# Arduino101BiomedDevBoard.net
KiCad netlist of a schematic drawn in EAGLE
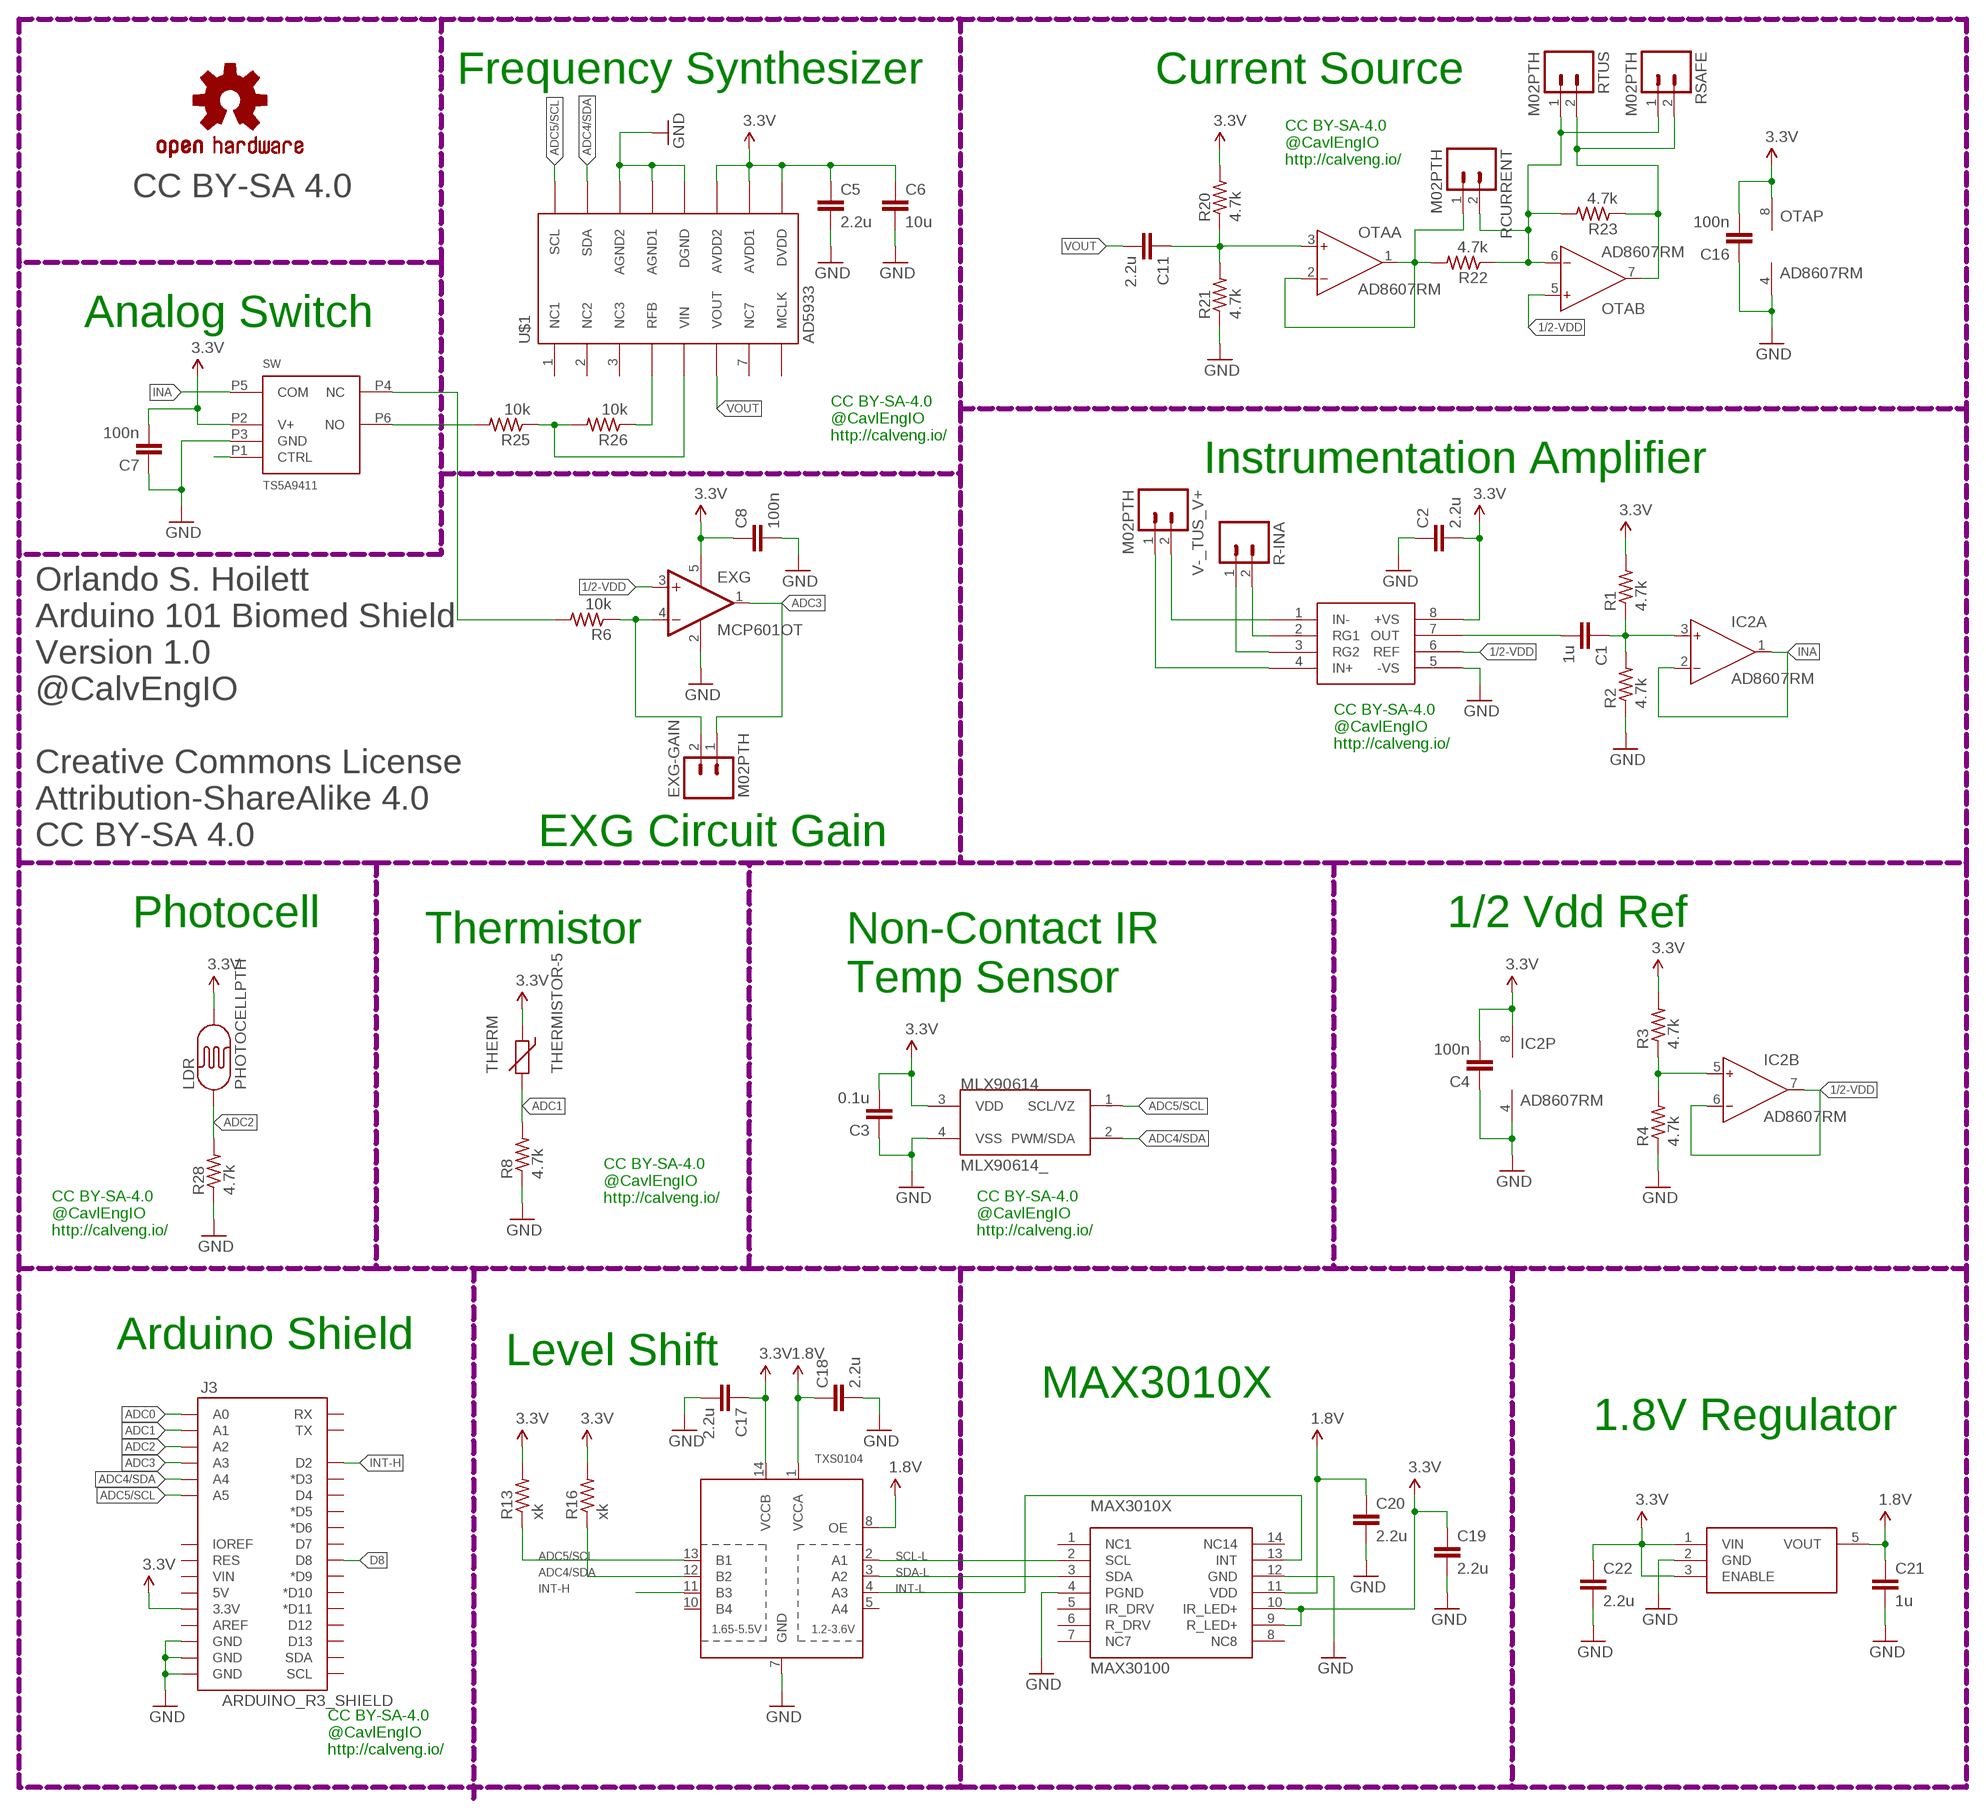
[diagram p0: schematic, sheet 1]

(export (version "E")
  (design (tool "Eeschema 10.0.6"))
  (components
    (comp (ref "1.8V")
      (value "MIC5504")
      (footprint "eagle-import:SOT23-5")
      (libsource (lib "eagle-import") (part "MIC5504"))
    )
    (comp (ref "C1")
      (value "1u")
      (footprint "eagle-import:C0402")
      (libsource (lib "eagle-import") (part "C-EUC0402"))
    )
    (comp (ref "C2")
      (value "2.2u")
      (footprint "eagle-import:C0402")
      (libsource (lib "eagle-import") (part "C-EUC0402"))
    )
    (comp (ref "C3")
      (value "0.1u")
      (footprint "eagle-import:C0402")
      (libsource (lib "eagle-import") (part "C-EUC0402"))
    )
    (comp (ref "C4")
      (value "100n")
      (footprint "eagle-import:C0402")
      (libsource (lib "eagle-import") (part "C-EUC0402"))
    )
    (comp (ref "C5")
      (value "2.2u")
      (footprint "eagle-import:C0402")
      (libsource (lib "eagle-import") (part "C-EUC0402"))
    )
    (comp (ref "C6")
      (value "10u")
      (footprint "eagle-import:C0805")
      (libsource (lib "eagle-import") (part "C-EUC0805"))
    )
    (comp (ref "C7")
      (value "100n")
      (footprint "eagle-import:C0402")
      (libsource (lib "eagle-import") (part "C-EUC0402"))
    )
    (comp (ref "C8")
      (value "100n")
      (footprint "eagle-import:C0402")
      (libsource (lib "eagle-import") (part "C-EUC0402"))
    )
    (comp (ref "C11")
      (value "2.2u")
      (footprint "eagle-import:C0402")
      (libsource (lib "eagle-import") (part "C-EUC0402"))
    )
    (comp (ref "C16")
      (value "100n")
      (footprint "eagle-import:C0402")
      (libsource (lib "eagle-import") (part "C-EUC0402"))
    )
    (comp (ref "C17")
      (value "2.2u")
      (footprint "eagle-import:C0402")
      (libsource (lib "eagle-import") (part "C-EUC0402"))
    )
    (comp (ref "C18")
      (value "2.2u")
      (footprint "eagle-import:C0402")
      (libsource (lib "eagle-import") (part "C-EUC0402"))
    )
    (comp (ref "C19")
      (value "2.2u")
      (footprint "eagle-import:C0402")
      (libsource (lib "eagle-import") (part "C-EUC0402"))
    )
    (comp (ref "C20")
      (value "2.2u")
      (footprint "eagle-import:C0402")
      (libsource (lib "eagle-import") (part "C-EUC0402"))
    )
    (comp (ref "C21")
      (value "1u")
      (footprint "eagle-import:C0402")
      (libsource (lib "eagle-import") (part "C-EUC0402"))
    )
    (comp (ref "C22")
      (value "2.2u")
      (footprint "eagle-import:C0402")
      (libsource (lib "eagle-import") (part "C-EUC0402"))
    )
    (comp (ref "EXG")
      (value "MCP601OT")
      (footprint "eagle-import:SOT23-5")
      (libsource (lib "eagle-import") (part "MCP601OT"))
    )
    (comp (ref "EXG-GAIN")
      (value "M02PTH")
      (footprint "eagle-import:1X02")
      (libsource (lib "eagle-import") (part "M02PTH"))
    )
    (comp (ref "IC2")
      (value "AD8607RM")
      (footprint "eagle-import:MSOP08")
      (fields (field (name "MF") "ALTERA CORPORATION") (field (name "MPN") "AD8607ARMZ-REEL"))
      (libsource (lib "eagle-import") (part "AD8607RM"))
    )
    (comp (ref "INA")
      (value "AD8220")
      (footprint "eagle-import:MSOP08")
      (libsource (lib "eagle-import") (part "AD8220"))
    )
    (comp (ref "J3")
      (value "ARDUINO_R3_SHIELD")
      (footprint "eagle-import:UNO_R3_SHIELD")
      (libsource (lib "eagle-import") (part "ARDUINO_R3_SHIELD"))
    )
    (comp (ref "LDR")
      (value "PHOTOCELLPTH")
      (footprint "eagle-import:PHOTOCELL")
      (libsource (lib "eagle-import") (part "PHOTOCELLPTH"))
    )
    (comp (ref "LOGO3")
      (value "OSHW-LOGOM")
      (footprint "eagle-import:OSHW-LOGO-M")
      (libsource (lib "eagle-import") (part "OSHW-LOGOM"))
    )
    (comp (ref "MAX3010X")
      (value "MAX30100")
      (footprint "eagle-import:OESIP14")
      (libsource (lib "eagle-import") (part "MAX30100"))
    )
    (comp (ref "MLX90614")
      (value "MLX90614_")
      (footprint "eagle-import:TO-39")
      (libsource (lib "eagle-import") (part "MLX90614_"))
    )
    (comp (ref "OTA")
      (value "AD8607RM")
      (footprint "eagle-import:MSOP08")
      (fields (field (name "MF") "ALTERA CORPORATION") (field (name "MPN") "AD8607ARMZ-REEL"))
      (libsource (lib "eagle-import") (part "AD8607RM"))
    )
    (comp (ref "R-INA")
      (value "M02PTH")
      (footprint "eagle-import:1X02")
      (libsource (lib "eagle-import") (part "M02PTH"))
    )
    (comp (ref "R1")
      (value "4.7k")
      (footprint "eagle-import:R0402")
      (libsource (lib "eagle-import") (part "R-US_R0402"))
    )
    (comp (ref "R2")
      (value "4.7k")
      (footprint "eagle-import:R0402")
      (libsource (lib "eagle-import") (part "R-US_R0402"))
    )
    (comp (ref "R3")
      (value "4.7k")
      (footprint "eagle-import:R0402")
      (libsource (lib "eagle-import") (part "R-US_R0402"))
    )
    (comp (ref "R4")
      (value "4.7k")
      (footprint "eagle-import:R0402")
      (libsource (lib "eagle-import") (part "R-US_R0402"))
    )
    (comp (ref "R6")
      (value "10k")
      (footprint "eagle-import:R0402")
      (libsource (lib "eagle-import") (part "R-US_R0402"))
    )
    (comp (ref "R8")
      (value "4.7k")
      (footprint "eagle-import:R0402")
      (libsource (lib "eagle-import") (part "R-US_R0402"))
    )
    (comp (ref "R13")
      (value "xk")
      (footprint "eagle-import:R0402")
      (libsource (lib "eagle-import") (part "R-US_R0402"))
    )
    (comp (ref "R16")
      (value "xk")
      (footprint "eagle-import:R0402")
      (libsource (lib "eagle-import") (part "R-US_R0402"))
    )
    (comp (ref "R20")
      (value "4.7k")
      (footprint "eagle-import:R0402")
      (libsource (lib "eagle-import") (part "R-US_R0402"))
    )
    (comp (ref "R21")
      (value "4.7k")
      (footprint "eagle-import:R0402")
      (libsource (lib "eagle-import") (part "R-US_R0402"))
    )
    (comp (ref "R22")
      (value "4.7k")
      (footprint "eagle-import:R0402")
      (libsource (lib "eagle-import") (part "R-US_R0402"))
    )
    (comp (ref "R23")
      (value "4.7k")
      (footprint "eagle-import:R0402")
      (libsource (lib "eagle-import") (part "R-US_R0402"))
    )
    (comp (ref "R25")
      (value "10k")
      (footprint "eagle-import:R0402")
      (libsource (lib "eagle-import") (part "R-US_R0402"))
    )
    (comp (ref "R26")
      (value "10k")
      (footprint "eagle-import:R0402")
      (libsource (lib "eagle-import") (part "R-US_R0402"))
    )
    (comp (ref "R28")
      (value "4.7k")
      (footprint "eagle-import:R0402")
      (libsource (lib "eagle-import") (part "R-US_R0402"))
    )
    (comp (ref "RCURRENT")
      (value "M02PTH")
      (footprint "eagle-import:1X02")
      (libsource (lib "eagle-import") (part "M02PTH"))
    )
    (comp (ref "RSAFE")
      (value "M02PTH")
      (footprint "eagle-import:1X02")
      (libsource (lib "eagle-import") (part "M02PTH"))
    )
    (comp (ref "RTUS")
      (value "M02PTH")
      (footprint "eagle-import:1X02")
      (libsource (lib "eagle-import") (part "M02PTH"))
    )
    (comp (ref "SW")
      (value "TS5A9411")
      (footprint "eagle-import:SOT-363")
      (libsource (lib "eagle-import") (part "TS5A9411"))
    )
    (comp (ref "THERM")
      (value "THERMISTOR-5")
      (footprint "eagle-import:R-5")
      (libsource (lib "eagle-import") (part "THERMISTOR-5"))
    )
    (comp (ref "TXS0104")
      (value "TXB0104PWR")
      (footprint "eagle-import:TSSOP14")
      (libsource (lib "eagle-import") (part "TXB0104PWR"))
    )
    (comp (ref "U$1")
      (value "AD5933")
      (footprint "eagle-import:SSOP-16")
      (libsource (lib "eagle-import") (part "AD5933"))
    )
    (comp (ref "V-_TUS_V+")
      (value "M02PTH")
      (footprint "eagle-import:1X02")
      (libsource (lib "eagle-import") (part "M02PTH"))
    )
  )
  (nets
    (net (code "1") (name "/INT-L") (class "Default")
      (node (ref "MAX3010X") (pin "13") (pinfunction "INT_13") (pintype "bidirectional"))
      (node (ref "TXS0104") (pin "4") (pinfunction "A3_4") (pintype "bidirectional"))
    )
    (net (code "2") (name "/SCL-L") (class "Default")
      (node (ref "MAX3010X") (pin "2") (pinfunction "SCL_2") (pintype "bidirectional"))
      (node (ref "TXS0104") (pin "2") (pinfunction "A1_2") (pintype "bidirectional"))
    )
    (net (code "3") (name "/SDA-L") (class "Default")
      (node (ref "MAX3010X") (pin "3") (pinfunction "SDA_3") (pintype "bidirectional"))
      (node (ref "TXS0104") (pin "3") (pinfunction "A2_3") (pintype "bidirectional"))
    )
    (net (code "4") (name "1.8V") (class "Default")
      (node (ref "1.8V") (pin "5") (pinfunction "VOUT_5") (pintype "bidirectional"))
      (node (ref "C18") (pin "1") (pinfunction "1_1") (pintype "passive"))
      (node (ref "C20") (pin "1") (pinfunction "1_1") (pintype "passive"))
      (node (ref "C21") (pin "1") (pinfunction "1_1") (pintype "passive"))
      (node (ref "MAX3010X") (pin "11") (pinfunction "VDD_11") (pintype "bidirectional"))
      (node (ref "TXS0104") (pin "1") (pinfunction "VCCA_1") (pintype "bidirectional"))
      (node (ref "TXS0104") (pin "8") (pinfunction "OE_8") (pintype "bidirectional"))
    )
    (net (code "5") (name "1{slash}2-VDD") (class "Default")
      (node (ref "EXG") (pin "3") (pinfunction "+IN_3") (pintype "input"))
      (node (ref "IC2") (pin "6") (pinfunction "IN-_6") (pintype "input"))
      (node (ref "IC2") (pin "7") (pinfunction "OUT_7") (pintype "output"))
      (node (ref "INA") (pin "6") (pinfunction "REF_6") (pintype "bidirectional"))
      (node (ref "OTA") (pin "5") (pinfunction "IN+_5") (pintype "input"))
    )
    (net (code "6") (name "3.3V") (class "Default")
      (node (ref "1.8V") (pin "1") (pinfunction "VIN_1") (pintype "bidirectional"))
      (node (ref "1.8V") (pin "3") (pinfunction "ENABLE_3") (pintype "bidirectional"))
      (node (ref "C16") (pin "2") (pinfunction "2_2") (pintype "passive"))
      (node (ref "C17") (pin "1") (pinfunction "1_1") (pintype "passive"))
      (node (ref "C19") (pin "1") (pinfunction "1_1") (pintype "passive"))
      (node (ref "C2") (pin "2") (pinfunction "2_2") (pintype "passive"))
      (node (ref "C22") (pin "1") (pinfunction "1_1") (pintype "passive"))
      (node (ref "C3") (pin "2") (pinfunction "2_2") (pintype "passive"))
      (node (ref "C4") (pin "2") (pinfunction "2_2") (pintype "passive"))
      (node (ref "C5") (pin "1") (pinfunction "1_1") (pintype "passive"))
      (node (ref "C6") (pin "1") (pinfunction "1_1") (pintype "passive"))
      (node (ref "C7") (pin "2") (pinfunction "2_2") (pintype "passive"))
      (node (ref "C8") (pin "1") (pinfunction "1_1") (pintype "passive"))
      (node (ref "EXG") (pin "5") (pinfunction "V+_5") (pintype "power_in"))
      (node (ref "IC2") (pin "8") (pinfunction "V+_8") (pintype "power_in"))
      (node (ref "INA") (pin "8") (pinfunction "+VS_8") (pintype "bidirectional"))
      (node (ref "J3") (pin "3.3V") (pinfunction "3.3V_3.3V") (pintype "bidirectional"))
      (node (ref "LDR") (pin "2") (pinfunction "P$2_2") (pintype "bidirectional"))
      (node (ref "MAX3010X") (pin "10") (pinfunction "IR_LED+_10") (pintype "bidirectional"))
      (node (ref "MAX3010X") (pin "9") (pinfunction "R_LED+_9") (pintype "bidirectional"))
      (node (ref "MLX90614") (pin "3") (pinfunction "VDD_3") (pintype "bidirectional"))
      (node (ref "OTA") (pin "8") (pinfunction "V+_8") (pintype "power_in"))
      (node (ref "R1") (pin "2") (pinfunction "2_2") (pintype "passive"))
      (node (ref "R13") (pin "2") (pinfunction "2_2") (pintype "passive"))
      (node (ref "R16") (pin "2") (pinfunction "2_2") (pintype "passive"))
      (node (ref "R20") (pin "2") (pinfunction "2_2") (pintype "passive"))
      (node (ref "R3") (pin "2") (pinfunction "2_2") (pintype "passive"))
      (node (ref "SW") (pin "P2") (pinfunction "V+_P2") (pintype "bidirectional"))
      (node (ref "THERM") (pin "1") (pinfunction "1_1") (pintype "passive"))
      (node (ref "TXS0104") (pin "14") (pinfunction "VCCB_14") (pintype "bidirectional"))
      (node (ref "U$1") (pin "10") (pinfunction "AVDD1_10") (pintype "bidirectional"))
      (node (ref "U$1") (pin "11") (pinfunction "AVDD2_11") (pintype "bidirectional"))
      (node (ref "U$1") (pin "9") (pinfunction "DVDD_9") (pintype "bidirectional"))
    )
    (net (code "7") (name "ADC0") (class "Default")
      (node (ref "J3") (pin "A0") (pinfunction "A0_A0") (pintype "bidirectional"))
    )
    (net (code "8") (name "ADC1") (class "Default")
      (node (ref "J3") (pin "A1") (pinfunction "A1_A1") (pintype "bidirectional"))
      (node (ref "R8") (pin "2") (pinfunction "2_2") (pintype "passive"))
      (node (ref "THERM") (pin "2") (pinfunction "2_2") (pintype "passive"))
    )
    (net (code "9") (name "ADC2") (class "Default")
      (node (ref "J3") (pin "A2") (pinfunction "A2_A2") (pintype "bidirectional"))
      (node (ref "LDR") (pin "1") (pinfunction "P$1_1") (pintype "bidirectional"))
      (node (ref "R28") (pin "2") (pinfunction "2_2") (pintype "passive"))
    )
    (net (code "10") (name "ADC3") (class "Default")
      (node (ref "EXG") (pin "1") (pinfunction "OUT_1") (pintype "output"))
      (node (ref "EXG-GAIN") (pin "1") (pinfunction "1_1") (pintype "passive"))
      (node (ref "J3") (pin "A3") (pinfunction "A3_A3") (pintype "bidirectional"))
    )
    (net (code "11") (name "ADC4{slash}SDA") (class "Default")
      (node (ref "J3") (pin "A4") (pinfunction "A4_A4") (pintype "bidirectional"))
      (node (ref "MLX90614") (pin "2") (pinfunction "PWM/SDA_2") (pintype "bidirectional"))
      (node (ref "R16") (pin "1") (pinfunction "1_1") (pintype "passive"))
      (node (ref "TXS0104") (pin "12") (pinfunction "B2_12") (pintype "bidirectional"))
      (node (ref "U$1") (pin "15") (pinfunction "SDA_15") (pintype "bidirectional"))
    )
    (net (code "12") (name "ADC5{slash}SCL") (class "Default")
      (node (ref "J3") (pin "A5") (pinfunction "A5_A5") (pintype "bidirectional"))
      (node (ref "MLX90614") (pin "1") (pinfunction "SCL/VZ_1") (pintype "bidirectional"))
      (node (ref "R13") (pin "1") (pinfunction "1_1") (pintype "passive"))
      (node (ref "TXS0104") (pin "13") (pinfunction "B1_13") (pintype "bidirectional"))
      (node (ref "U$1") (pin "16") (pinfunction "SCL_16") (pintype "bidirectional"))
    )
    (net (code "13") (name "D8") (class "Default")
      (node (ref "J3") (pin "D8") (pinfunction "D8_D8") (pintype "bidirectional"))
      (node (ref "SW") (pin "P1") (pinfunction "CTRL_P1") (pintype "bidirectional"))
    )
    (net (code "14") (name "GND") (class "Default")
      (node (ref "1.8V") (pin "2") (pinfunction "GND_2") (pintype "bidirectional"))
      (node (ref "C16") (pin "1") (pinfunction "1_1") (pintype "passive"))
      (node (ref "C17") (pin "2") (pinfunction "2_2") (pintype "passive"))
      (node (ref "C18") (pin "2") (pinfunction "2_2") (pintype "passive"))
      (node (ref "C19") (pin "2") (pinfunction "2_2") (pintype "passive"))
      (node (ref "C2") (pin "1") (pinfunction "1_1") (pintype "passive"))
      (node (ref "C20") (pin "2") (pinfunction "2_2") (pintype "passive"))
      (node (ref "C21") (pin "2") (pinfunction "2_2") (pintype "passive"))
      (node (ref "C22") (pin "2") (pinfunction "2_2") (pintype "passive"))
      (node (ref "C3") (pin "1") (pinfunction "1_1") (pintype "passive"))
      (node (ref "C4") (pin "1") (pinfunction "1_1") (pintype "passive"))
      (node (ref "C5") (pin "2") (pinfunction "2_2") (pintype "passive"))
      (node (ref "C6") (pin "2") (pinfunction "2_2") (pintype "passive"))
      (node (ref "C7") (pin "1") (pinfunction "1_1") (pintype "passive"))
      (node (ref "C8") (pin "2") (pinfunction "2_2") (pintype "passive"))
      (node (ref "EXG") (pin "2") (pinfunction "V-_2") (pintype "power_in"))
      (node (ref "IC2") (pin "4") (pinfunction "V-_4") (pintype "power_in"))
      (node (ref "INA") (pin "5") (pinfunction "-VS_5") (pintype "bidirectional"))
      (node (ref "J3") (pin "GND@0") (pinfunction "GND_GND@0") (pintype "bidirectional"))
      (node (ref "J3") (pin "GND@1") (pinfunction "GND_GND@1") (pintype "bidirectional"))
      (node (ref "J3") (pin "GND@2") (pinfunction "GND_GND@2") (pintype "bidirectional"))
      (node (ref "MAX3010X") (pin "12") (pinfunction "GND_12") (pintype "bidirectional"))
      (node (ref "MAX3010X") (pin "4") (pinfunction "PGND_4") (pintype "bidirectional"))
      (node (ref "MLX90614") (pin "4") (pinfunction "VSS_4") (pintype "bidirectional"))
      (node (ref "OTA") (pin "4") (pinfunction "V-_4") (pintype "power_in"))
      (node (ref "R2") (pin "1") (pinfunction "1_1") (pintype "passive"))
      (node (ref "R21") (pin "1") (pinfunction "1_1") (pintype "passive"))
      (node (ref "R28") (pin "1") (pinfunction "1_1") (pintype "passive"))
      (node (ref "R4") (pin "1") (pinfunction "1_1") (pintype "passive"))
      (node (ref "R8") (pin "1") (pinfunction "1_1") (pintype "passive"))
      (node (ref "SW") (pin "P3") (pinfunction "GND_P3") (pintype "bidirectional"))
      (node (ref "TXS0104") (pin "7") (pinfunction "GND_7") (pintype "bidirectional"))
      (node (ref "U$1") (pin "12") (pinfunction "DGND_12") (pintype "bidirectional"))
      (node (ref "U$1") (pin "13") (pinfunction "AGND1_13") (pintype "bidirectional"))
      (node (ref "U$1") (pin "14") (pinfunction "AGND2_14") (pintype "bidirectional"))
    )
    (net (code "15") (name "INA") (class "Default")
      (node (ref "IC2") (pin "1") (pinfunction "OUT_1") (pintype "output"))
      (node (ref "IC2") (pin "2") (pinfunction "IN-_2") (pintype "input"))
      (node (ref "SW") (pin "P5") (pinfunction "COM_P5") (pintype "bidirectional"))
    )
    (net (code "16") (name "INT-H") (class "Default")
      (node (ref "J3") (pin "D2") (pinfunction "D2_D2") (pintype "bidirectional"))
      (node (ref "TXS0104") (pin "11") (pinfunction "B3_11") (pintype "bidirectional"))
    )
    (net (code "17") (name "Net-(EXG--IN)") (class "Default")
      (node (ref "EXG") (pin "4") (pinfunction "-IN_4") (pintype "input"))
      (node (ref "EXG-GAIN") (pin "2") (pinfunction "2_2") (pintype "passive"))
      (node (ref "R6") (pin "1") (pinfunction "1_1") (pintype "passive"))
    )
    (net (code "18") (name "Net-(IC2A-IN+)") (class "Default")
      (node (ref "C1") (pin "1") (pinfunction "1_1") (pintype "passive"))
      (node (ref "IC2") (pin "3") (pinfunction "IN+_3") (pintype "input"))
      (node (ref "R1") (pin "1") (pinfunction "1_1") (pintype "passive"))
      (node (ref "R2") (pin "2") (pinfunction "2_2") (pintype "passive"))
    )
    (net (code "19") (name "Net-(IC2B-IN+)") (class "Default")
      (node (ref "IC2") (pin "5") (pinfunction "IN+_5") (pintype "input"))
      (node (ref "R3") (pin "1") (pinfunction "1_1") (pintype "passive"))
      (node (ref "R4") (pin "2") (pinfunction "2_2") (pintype "passive"))
    )
    (net (code "20") (name "Net-(INA-IN+)") (class "Default")
      (node (ref "INA") (pin "4") (pinfunction "IN+_4") (pintype "bidirectional"))
      (node (ref "V-_TUS_V+") (pin "1") (pinfunction "1_1") (pintype "passive"))
    )
    (net (code "21") (name "Net-(INA-IN-)") (class "Default")
      (node (ref "INA") (pin "1") (pinfunction "IN-_1") (pintype "bidirectional"))
      (node (ref "V-_TUS_V+") (pin "2") (pinfunction "2_2") (pintype "passive"))
    )
    (net (code "22") (name "Net-(INA-OUT)") (class "Default")
      (node (ref "C1") (pin "2") (pinfunction "2_2") (pintype "passive"))
      (node (ref "INA") (pin "7") (pinfunction "OUT_7") (pintype "bidirectional"))
    )
    (net (code "23") (name "Net-(INA-RG1)") (class "Default")
      (node (ref "INA") (pin "2") (pinfunction "RG1_2") (pintype "bidirectional"))
      (node (ref "R-INA") (pin "2") (pinfunction "2_2") (pintype "passive"))
    )
    (net (code "24") (name "Net-(INA-RG2)") (class "Default")
      (node (ref "INA") (pin "3") (pinfunction "RG2_3") (pintype "bidirectional"))
      (node (ref "R-INA") (pin "1") (pinfunction "1_1") (pintype "passive"))
    )
    (net (code "25") (name "Net-(OTAA-IN+)") (class "Default")
      (node (ref "C11") (pin "1") (pinfunction "1_1") (pintype "passive"))
      (node (ref "OTA") (pin "3") (pinfunction "IN+_3") (pintype "input"))
      (node (ref "R20") (pin "1") (pinfunction "1_1") (pintype "passive"))
      (node (ref "R21") (pin "2") (pinfunction "2_2") (pintype "passive"))
    )
    (net (code "26") (name "Net-(OTAA-IN-)") (class "Default")
      (node (ref "OTA") (pin "1") (pinfunction "OUT_1") (pintype "output"))
      (node (ref "OTA") (pin "2") (pinfunction "IN-_2") (pintype "input"))
      (node (ref "R22") (pin "2") (pinfunction "2_2") (pintype "passive"))
      (node (ref "RCURRENT") (pin "1") (pinfunction "1_1") (pintype "passive"))
    )
    (net (code "27") (name "Net-(OTAB-IN-)") (class "Default")
      (node (ref "OTA") (pin "6") (pinfunction "IN-_6") (pintype "input"))
      (node (ref "R22") (pin "1") (pinfunction "1_1") (pintype "passive"))
      (node (ref "R23") (pin "2") (pinfunction "2_2") (pintype "passive"))
      (node (ref "RCURRENT") (pin "2") (pinfunction "2_2") (pintype "passive"))
      (node (ref "RSAFE") (pin "1") (pinfunction "1_1") (pintype "passive"))
      (node (ref "RTUS") (pin "1") (pinfunction "1_1") (pintype "passive"))
    )
    (net (code "28") (name "Net-(OTAB-OUT)") (class "Default")
      (node (ref "OTA") (pin "7") (pinfunction "OUT_7") (pintype "output"))
      (node (ref "R23") (pin "1") (pinfunction "1_1") (pintype "passive"))
      (node (ref "RSAFE") (pin "2") (pinfunction "2_2") (pintype "passive"))
      (node (ref "RTUS") (pin "2") (pinfunction "2_2") (pintype "passive"))
    )
    (net (code "29") (name "Net-(SW-NC)") (class "Default")
      (node (ref "R6") (pin "2") (pinfunction "2_2") (pintype "passive"))
      (node (ref "SW") (pin "P4") (pinfunction "NC_P4") (pintype "bidirectional"))
    )
    (net (code "30") (name "Net-(SW-NO)") (class "Default")
      (node (ref "R25") (pin "2") (pinfunction "2_2") (pintype "passive"))
      (node (ref "SW") (pin "P6") (pinfunction "NO_P6") (pintype "bidirectional"))
    )
    (net (code "31") (name "Net-(U$1-RFB)") (class "Default")
      (node (ref "R26") (pin "1") (pinfunction "1_1") (pintype "passive"))
      (node (ref "U$1") (pin "4") (pinfunction "RFB_4") (pintype "bidirectional"))
    )
    (net (code "32") (name "Net-(U$1-VIN)") (class "Default")
      (node (ref "R25") (pin "1") (pinfunction "1_1") (pintype "passive"))
      (node (ref "R26") (pin "2") (pinfunction "2_2") (pintype "passive"))
      (node (ref "U$1") (pin "5") (pinfunction "VIN_5") (pintype "bidirectional"))
    )
    (net (code "33") (name "VOUT") (class "Default")
      (node (ref "C11") (pin "2") (pinfunction "2_2") (pintype "passive"))
      (node (ref "U$1") (pin "6") (pinfunction "VOUT_6") (pintype "bidirectional"))
    )
    (net (code "34") (name "unconnected-(J3-*D3-PadD3)") (class "Default")
      (node (ref "J3") (pin "D3") (pinfunction "*D3_D3") (pintype "bidirectional"))
    )
    (net (code "35") (name "unconnected-(J3-*D5-PadD5)") (class "Default")
      (node (ref "J3") (pin "D5") (pinfunction "*D5_D5") (pintype "bidirectional"))
    )
    (net (code "36") (name "unconnected-(J3-*D6-PadD6)") (class "Default")
      (node (ref "J3") (pin "D6") (pinfunction "*D6_D6") (pintype "bidirectional"))
    )
    (net (code "37") (name "unconnected-(J3-*D9-PadD9)") (class "Default")
      (node (ref "J3") (pin "D9") (pinfunction "*D9_D9") (pintype "bidirectional"))
    )
    (net (code "38") (name "unconnected-(J3-*D10-PadD10)") (class "Default")
      (node (ref "J3") (pin "D10") (pinfunction "*D10_D10") (pintype "bidirectional"))
    )
    (net (code "39") (name "unconnected-(J3-*D11-PadD11)") (class "Default")
      (node (ref "J3") (pin "D11") (pinfunction "*D11_D11") (pintype "bidirectional"))
    )
    (net (code "40") (name "unconnected-(J3-Pad5V)") (class "Default")
      (node (ref "J3") (pin "5V") (pinfunction "5V_5V") (pintype "bidirectional"))
    )
    (net (code "41") (name "unconnected-(J3-PadAREF)") (class "Default")
      (node (ref "J3") (pin "AREF") (pinfunction "AREF_AREF") (pintype "bidirectional"))
    )
    (net (code "42") (name "unconnected-(J3-PadD4)") (class "Default")
      (node (ref "J3") (pin "D4") (pinfunction "D4_D4") (pintype "bidirectional"))
    )
    (net (code "43") (name "unconnected-(J3-PadD7)") (class "Default")
      (node (ref "J3") (pin "D7") (pinfunction "D7_D7") (pintype "bidirectional"))
    )
    (net (code "44") (name "unconnected-(J3-PadD12)") (class "Default")
      (node (ref "J3") (pin "D12") (pinfunction "D12_D12") (pintype "bidirectional"))
    )
    (net (code "45") (name "unconnected-(J3-PadD13)") (class "Default")
      (node (ref "J3") (pin "D13") (pinfunction "D13_D13") (pintype "bidirectional"))
    )
    (net (code "46") (name "unconnected-(J3-PadIOREF)") (class "Default")
      (node (ref "J3") (pin "IOREF") (pinfunction "IOREF_IOREF") (pintype "bidirectional"))
    )
    (net (code "47") (name "unconnected-(J3-PadRES)") (class "Default")
      (node (ref "J3") (pin "RES") (pinfunction "RES_RES") (pintype "bidirectional"))
    )
    (net (code "48") (name "unconnected-(J3-PadRX)") (class "Default")
      (node (ref "J3") (pin "RX") (pinfunction "RX_RX") (pintype "bidirectional"))
    )
    (net (code "49") (name "unconnected-(J3-PadSCL)") (class "Default")
      (node (ref "J3") (pin "SCL") (pinfunction "SCL_SCL") (pintype "bidirectional"))
    )
    (net (code "50") (name "unconnected-(J3-PadSDA)") (class "Default")
      (node (ref "J3") (pin "SDA") (pinfunction "SDA_SDA") (pintype "bidirectional"))
    )
    (net (code "51") (name "unconnected-(J3-PadTX)") (class "Default")
      (node (ref "J3") (pin "TX") (pinfunction "TX_TX") (pintype "bidirectional"))
    )
    (net (code "52") (name "unconnected-(J3-PadVIN)") (class "Default")
      (node (ref "J3") (pin "VIN") (pinfunction "VIN_VIN") (pintype "bidirectional"))
    )
    (net (code "53") (name "unconnected-(MAX3010X-IR_DRV-Pad5)") (class "Default")
      (node (ref "MAX3010X") (pin "5") (pinfunction "IR_DRV_5") (pintype "bidirectional"))
    )
    (net (code "54") (name "unconnected-(MAX3010X-NC1-Pad1)") (class "Default")
      (node (ref "MAX3010X") (pin "1") (pinfunction "NC1_1") (pintype "bidirectional"))
    )
    (net (code "55") (name "unconnected-(MAX3010X-NC7-Pad7)") (class "Default")
      (node (ref "MAX3010X") (pin "7") (pinfunction "NC7_7") (pintype "bidirectional"))
    )
    (net (code "56") (name "unconnected-(MAX3010X-NC8-Pad8)") (class "Default")
      (node (ref "MAX3010X") (pin "8") (pinfunction "NC8_8") (pintype "bidirectional"))
    )
    (net (code "57") (name "unconnected-(MAX3010X-NC14-Pad14)") (class "Default")
      (node (ref "MAX3010X") (pin "14") (pinfunction "NC14_14") (pintype "bidirectional"))
    )
    (net (code "58") (name "unconnected-(MAX3010X-R_DRV-Pad6)") (class "Default")
      (node (ref "MAX3010X") (pin "6") (pinfunction "R_DRV_6") (pintype "bidirectional"))
    )
    (net (code "59") (name "unconnected-(TXS0104-A4-Pad5)") (class "Default")
      (node (ref "TXS0104") (pin "5") (pinfunction "A4_5") (pintype "bidirectional"))
    )
    (net (code "60") (name "unconnected-(TXS0104-B4-Pad10)") (class "Default")
      (node (ref "TXS0104") (pin "10") (pinfunction "B4_10") (pintype "bidirectional"))
    )
    (net (code "61") (name "unconnected-(U$1-MCLK-Pad8)") (class "Default")
      (node (ref "U$1") (pin "8") (pinfunction "MCLK_8") (pintype "bidirectional"))
    )
    (net (code "62") (name "unconnected-(U$1-NC1-Pad1)") (class "Default")
      (node (ref "U$1") (pin "1") (pinfunction "NC1_1") (pintype "bidirectional"))
    )
    (net (code "63") (name "unconnected-(U$1-NC2-Pad2)") (class "Default")
      (node (ref "U$1") (pin "2") (pinfunction "NC2_2") (pintype "bidirectional"))
    )
    (net (code "64") (name "unconnected-(U$1-NC3-Pad3)") (class "Default")
      (node (ref "U$1") (pin "3") (pinfunction "NC3_3") (pintype "bidirectional"))
    )
    (net (code "65") (name "unconnected-(U$1-NC7-Pad7)") (class "Default")
      (node (ref "U$1") (pin "7") (pinfunction "NC7_7") (pintype "bidirectional"))
    )
  )
)
